# VESC_KS75600_main_power.net
KiCad netlist of a schematic drawn in Altium Designer
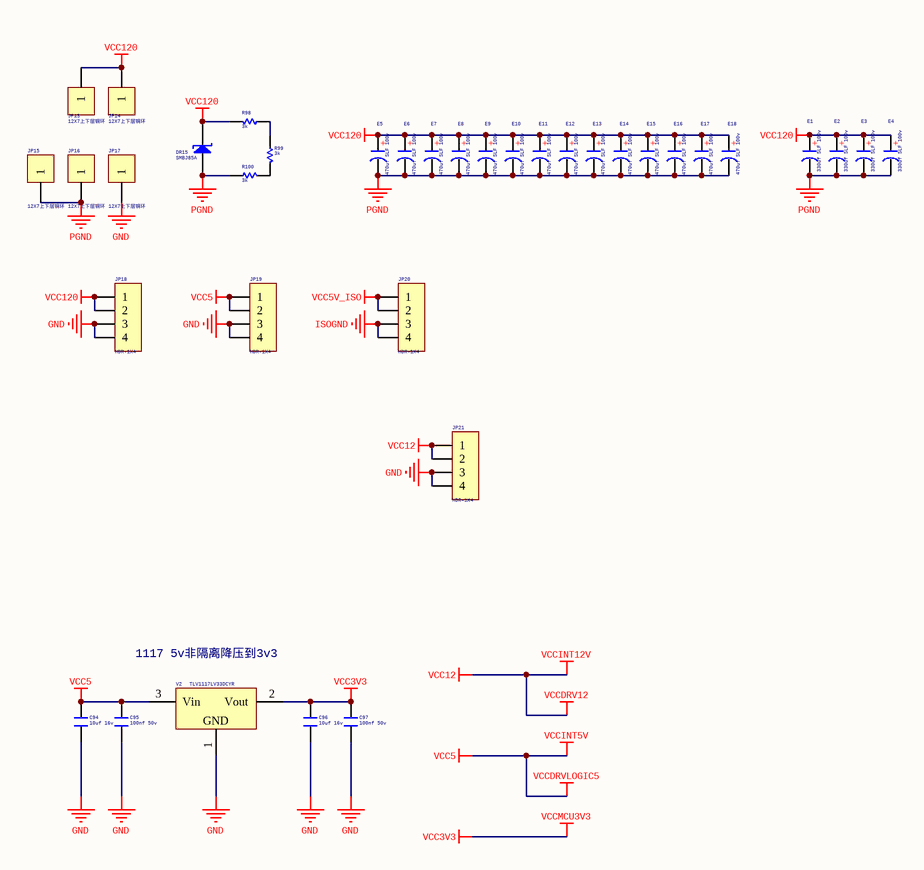
[diagram p0: VESC_KS75600_main_power.SchDoc]

(export (version "E")
  (design (tool "Eeschema 10.0.6"))
  (components
    (comp (ref "C94")
      (value "10uf 16v")
      (footprint "C 0805")
      (description "无极性贴片电容")
      (fields (field (name "VOLTAGE") "16v"))
      (libsource (lib "电阻-电容-电感") (part "C"))
    )
    (comp (ref "C95")
      (value "100nf 50v")
      (footprint "C 0603")
      (description "无极性贴片电容")
      (fields (field (name "VOLTAGE") "50v"))
      (libsource (lib "电阻-电容-电感") (part "C"))
    )
    (comp (ref "C96")
      (value "10uf 16v")
      (footprint "C 0805")
      (description "无极性贴片电容")
      (fields (field (name "VOLTAGE") "16v"))
      (libsource (lib "电阻-电容-电感") (part "C"))
    )
    (comp (ref "C97")
      (value "100nf 50v")
      (footprint "C 0603")
      (description "无极性贴片电容")
      (fields (field (name "VOLTAGE") "50v"))
      (libsource (lib "电阻-电容-电感") (part "C"))
    )
    (comp (ref "DR15")
      (value "SMBJ85A")
      (footprint "SMB")
      (description "瞬态电压抑制二极管(单向)")
      (libsource (lib "二极管-整流桥") (part "DR_S"))
    )
    (comp (ref "E1")
      (value "330uf SLF 100v")
      (footprint "CAP 5.0*13.5*26")
      (description "直插电解电容")
      (fields (field (name "VOLTAGE") "100v"))
      (libsource (lib "电阻-电容-电感") (part "C-CAP"))
    )
    (comp (ref "E2")
      (value "330uf SLF 100v")
      (footprint "CAP 5.0*13.5*26")
      (description "直插电解电容")
      (fields (field (name "VOLTAGE") "100v"))
      (libsource (lib "电阻-电容-电感") (part "C-CAP"))
    )
    (comp (ref "E3")
      (value "330uf SLF 100v")
      (footprint "CAP 5.0*13.5*26")
      (description "直插电解电容")
      (fields (field (name "VOLTAGE") "100v"))
      (libsource (lib "电阻-电容-电感") (part "C-CAP"))
    )
    (comp (ref "E4")
      (value "330uf SLF 100v")
      (footprint "CAP 5.0*13.5*26")
      (description "直插电解电容")
      (fields (field (name "VOLTAGE") "100v"))
      (libsource (lib "电阻-电容-电感") (part "C-CAP"))
    )
    (comp (ref "E5")
      (value "470uf SLF 100v")
      (footprint "CAP 7.5*16.5*27")
      (description "直插电解电容")
      (fields (field (name "VOLTAGE") "100v"))
      (libsource (lib "电阻-电容-电感") (part "C-CAP"))
    )
    (comp (ref "E6")
      (value "470uf SLF 100v")
      (footprint "CAP 7.5*16.5*27")
      (description "直插电解电容")
      (fields (field (name "VOLTAGE") "100v"))
      (libsource (lib "电阻-电容-电感") (part "C-CAP"))
    )
    (comp (ref "E7")
      (value "470uf SLF 100v")
      (footprint "CAP 7.5*16.5*27")
      (description "直插电解电容")
      (fields (field (name "VOLTAGE") "100v"))
      (libsource (lib "电阻-电容-电感") (part "C-CAP"))
    )
    (comp (ref "E8")
      (value "470uf SLF 100v")
      (footprint "CAP 7.5*16.5*27")
      (description "直插电解电容")
      (fields (field (name "VOLTAGE") "100v"))
      (libsource (lib "电阻-电容-电感") (part "C-CAP"))
    )
    (comp (ref "E9")
      (value "470uf SLF 100v")
      (footprint "CAP 7.5*16.5*27")
      (description "直插电解电容")
      (fields (field (name "VOLTAGE") "100v"))
      (libsource (lib "电阻-电容-电感") (part "C-CAP"))
    )
    (comp (ref "E10")
      (value "470uf SLF 100v")
      (footprint "CAP 7.5*16.5*27")
      (description "直插电解电容")
      (fields (field (name "VOLTAGE") "100v"))
      (libsource (lib "电阻-电容-电感") (part "C-CAP"))
    )
    (comp (ref "E11")
      (value "470uf SLF 100v")
      (footprint "CAP 7.5*16.5*27")
      (description "直插电解电容")
      (fields (field (name "VOLTAGE") "100v"))
      (libsource (lib "电阻-电容-电感") (part "C-CAP"))
    )
    (comp (ref "E12")
      (value "470uf SLF 100v")
      (footprint "CAP 7.5*16.5*27")
      (description "直插电解电容")
      (fields (field (name "VOLTAGE") "100v"))
      (libsource (lib "电阻-电容-电感") (part "C-CAP"))
    )
    (comp (ref "E13")
      (value "470uf SLF 100v")
      (footprint "CAP 7.5*16.5*27")
      (description "直插电解电容")
      (fields (field (name "VOLTAGE") "100v"))
      (libsource (lib "电阻-电容-电感") (part "C-CAP"))
    )
    (comp (ref "E14")
      (value "470uf SLF 100v")
      (footprint "CAP 7.5*16.5*27")
      (description "直插电解电容")
      (fields (field (name "VOLTAGE") "100v"))
      (libsource (lib "电阻-电容-电感") (part "C-CAP"))
    )
    (comp (ref "E15")
      (value "470uf SLF 100v")
      (footprint "CAP 7.5*16.5*27")
      (description "直插电解电容")
      (fields (field (name "VOLTAGE") "100v"))
      (libsource (lib "电阻-电容-电感") (part "C-CAP"))
    )
    (comp (ref "E16")
      (value "470uf SLF 100v")
      (footprint "CAP 7.5*16.5*27")
      (description "直插电解电容")
      (fields (field (name "VOLTAGE") "100v"))
      (libsource (lib "电阻-电容-电感") (part "C-CAP"))
    )
    (comp (ref "E17")
      (value "470uf SLF 100v")
      (footprint "CAP 7.5*16.5*27")
      (description "直插电解电容")
      (fields (field (name "VOLTAGE") "100v"))
      (libsource (lib "电阻-电容-电感") (part "C-CAP"))
    )
    (comp (ref "E18")
      (value "470uf SLF 100v")
      (footprint "CAP 7.5*16.5*27")
      (description "直插电解电容")
      (fields (field (name "VOLTAGE") "100v"))
      (libsource (lib "电阻-电容-电感") (part "C-CAP"))
    )
    (comp (ref "JP13")
      (value "12X7上下层铜环")
      (footprint "12x7上下层铜环")
      (description "1P接插件")
      (libsource (lib "") (part "Header 1_1"))
    )
    (comp (ref "JP14")
      (value "12X7上下层铜环")
      (footprint "12x7上下层铜环")
      (description "1P接插件")
      (libsource (lib "") (part "Header 1_1"))
    )
    (comp (ref "JP15")
      (value "12X7上下层铜环")
      (footprint "12x7上下层铜环")
      (description "1P接插件")
      (libsource (lib "接插件") (part "Header 1"))
    )
    (comp (ref "JP16")
      (value "12X7上下层铜环")
      (footprint "12x7上下层铜环")
      (description "1P接插件")
      (libsource (lib "接插件") (part "Header 1"))
    )
    (comp (ref "JP17")
      (value "12X7上下层铜环")
      (footprint "12x7上下层铜环")
      (description "1P接插件")
      (libsource (lib "接插件") (part "Header 1"))
    )
    (comp (ref "JP18")
      (value "HDR-1X4")
      (footprint "HDR-1X4")
      (description "4P接插件")
      (libsource (lib "接插件") (part "Header 4"))
    )
    (comp (ref "JP19")
      (value "HDR-1X4")
      (footprint "HDR-1X4")
      (description "4P接插件")
      (libsource (lib "接插件") (part "Header 4"))
    )
    (comp (ref "JP20")
      (value "HDR-1X4")
      (footprint "HDR-1X4")
      (description "4P接插件")
      (libsource (lib "接插件") (part "Header 4"))
    )
    (comp (ref "JP21")
      (value "HDR-1X4")
      (footprint "HDR-1X4")
      (description "4P接插件")
      (libsource (lib "接插件") (part "Header 4"))
    )
    (comp (ref "R98")
      (value "3k")
      (footprint "R 2512")
      (description "贴片电阻")
      (libsource (lib "电阻-电容-电感") (part "R"))
    )
    (comp (ref "R99")
      (value "3k")
      (footprint "R 2512")
      (description "贴片电阻")
      (libsource (lib "电阻-电容-电感") (part "R"))
    )
    (comp (ref "R100")
      (value "3k")
      (footprint "R 2512")
      (description "贴片电阻")
      (libsource (lib "电阻-电容-电感") (part "R"))
    )
    (comp (ref "V2")
      (value "TLV1117LV33DCYR")
      (footprint "SOT223_L")
      (description "三端稳压芯片")
      (libsource (lib "IC芯片") (part "AMS1117"))
    )
  )
  (nets
    (net (code "1") (name "GND") (class "Default")
      (node (ref "C94") (pin "2") (pinfunction "2_2") (pintype "passive"))
      (node (ref "C95") (pin "2") (pinfunction "2_2") (pintype "passive"))
      (node (ref "C96") (pin "2") (pinfunction "2_2") (pintype "passive"))
      (node (ref "C97") (pin "2") (pinfunction "2_2") (pintype "passive"))
      (node (ref "JP17") (pin "1") (pinfunction "1_1") (pintype "passive"))
      (node (ref "JP18") (pin "3") (pinfunction "3_3") (pintype "passive"))
      (node (ref "JP18") (pin "4") (pinfunction "4_4") (pintype "passive"))
      (node (ref "JP19") (pin "3") (pinfunction "3_3") (pintype "passive"))
      (node (ref "JP19") (pin "4") (pinfunction "4_4") (pintype "passive"))
      (node (ref "JP21") (pin "3") (pinfunction "3_3") (pintype "passive"))
      (node (ref "JP21") (pin "4") (pinfunction "4_4") (pintype "passive"))
      (node (ref "V2") (pin "1") (pinfunction "GND_1") (pintype "passive"))
    )
    (net (code "2") (name "ISOGND") (class "Default")
      (node (ref "JP20") (pin "3") (pinfunction "3_3") (pintype "passive"))
      (node (ref "JP20") (pin "4") (pinfunction "4_4") (pintype "passive"))
    )
    (net (code "3") (name "Net-(R98-Pad1)") (class "Default")
      (node (ref "R98") (pin "1") (pinfunction "1_1") (pintype "passive"))
      (node (ref "R99") (pin "1") (pinfunction "1_1") (pintype "passive"))
    )
    (net (code "4") (name "Net-(R100-Pad2)") (class "Default")
      (node (ref "R100") (pin "2") (pinfunction "2_2") (pintype "passive"))
      (node (ref "R99") (pin "2") (pinfunction "2_2") (pintype "passive"))
    )
    (net (code "5") (name "PGND") (class "Default")
      (node (ref "DR15") (pin "1") (pinfunction "A_1") (pintype "passive"))
      (node (ref "E1") (pin "2") (pinfunction "2_2") (pintype "passive"))
      (node (ref "E10") (pin "2") (pinfunction "2_2") (pintype "passive"))
      (node (ref "E11") (pin "2") (pinfunction "2_2") (pintype "passive"))
      (node (ref "E12") (pin "2") (pinfunction "2_2") (pintype "passive"))
      (node (ref "E13") (pin "2") (pinfunction "2_2") (pintype "passive"))
      (node (ref "E14") (pin "2") (pinfunction "2_2") (pintype "passive"))
      (node (ref "E15") (pin "2") (pinfunction "2_2") (pintype "passive"))
      (node (ref "E16") (pin "2") (pinfunction "2_2") (pintype "passive"))
      (node (ref "E17") (pin "2") (pinfunction "2_2") (pintype "passive"))
      (node (ref "E18") (pin "2") (pinfunction "2_2") (pintype "passive"))
      (node (ref "E2") (pin "2") (pinfunction "2_2") (pintype "passive"))
      (node (ref "E3") (pin "2") (pinfunction "2_2") (pintype "passive"))
      (node (ref "E4") (pin "2") (pinfunction "2_2") (pintype "passive"))
      (node (ref "E5") (pin "2") (pinfunction "2_2") (pintype "passive"))
      (node (ref "E6") (pin "2") (pinfunction "2_2") (pintype "passive"))
      (node (ref "E7") (pin "2") (pinfunction "2_2") (pintype "passive"))
      (node (ref "E8") (pin "2") (pinfunction "2_2") (pintype "passive"))
      (node (ref "E9") (pin "2") (pinfunction "2_2") (pintype "passive"))
      (node (ref "JP15") (pin "1") (pinfunction "1_1") (pintype "passive"))
      (node (ref "JP16") (pin "1") (pinfunction "1_1") (pintype "passive"))
      (node (ref "R100") (pin "1") (pinfunction "1_1") (pintype "passive"))
    )
    (net (code "6") (name "VCC3V3") (class "Default")
      (node (ref "C96") (pin "1") (pinfunction "1_1") (pintype "passive"))
      (node (ref "C97") (pin "1") (pinfunction "1_1") (pintype "passive"))
      (node (ref "V2") (pin "2") (pinfunction "Vout_2") (pintype "passive"))
    )
    (net (code "7") (name "VCC5") (class "Default")
      (node (ref "C94") (pin "1") (pinfunction "1_1") (pintype "passive"))
      (node (ref "C95") (pin "1") (pinfunction "1_1") (pintype "passive"))
      (node (ref "JP19") (pin "1") (pinfunction "1_1") (pintype "passive"))
      (node (ref "JP19") (pin "2") (pinfunction "2_2") (pintype "passive"))
      (node (ref "V2") (pin "3") (pinfunction "Vin_3") (pintype "passive"))
    )
    (net (code "8") (name "VCC5V_ISO") (class "Default")
      (node (ref "JP20") (pin "1") (pinfunction "1_1") (pintype "passive"))
      (node (ref "JP20") (pin "2") (pinfunction "2_2") (pintype "passive"))
    )
    (net (code "9") (name "VCC12") (class "Default")
      (node (ref "JP21") (pin "1") (pinfunction "1_1") (pintype "passive"))
      (node (ref "JP21") (pin "2") (pinfunction "2_2") (pintype "passive"))
    )
    (net (code "10") (name "VCC120") (class "Default")
      (node (ref "DR15") (pin "2") (pinfunction "K_2") (pintype "passive"))
      (node (ref "E1") (pin "1") (pinfunction "1_1") (pintype "passive"))
      (node (ref "E10") (pin "1") (pinfunction "1_1") (pintype "passive"))
      (node (ref "E11") (pin "1") (pinfunction "1_1") (pintype "passive"))
      (node (ref "E12") (pin "1") (pinfunction "1_1") (pintype "passive"))
      (node (ref "E13") (pin "1") (pinfunction "1_1") (pintype "passive"))
      (node (ref "E14") (pin "1") (pinfunction "1_1") (pintype "passive"))
      (node (ref "E15") (pin "1") (pinfunction "1_1") (pintype "passive"))
      (node (ref "E16") (pin "1") (pinfunction "1_1") (pintype "passive"))
      (node (ref "E17") (pin "1") (pinfunction "1_1") (pintype "passive"))
      (node (ref "E18") (pin "1") (pinfunction "1_1") (pintype "passive"))
      (node (ref "E2") (pin "1") (pinfunction "1_1") (pintype "passive"))
      (node (ref "E3") (pin "1") (pinfunction "1_1") (pintype "passive"))
      (node (ref "E4") (pin "1") (pinfunction "1_1") (pintype "passive"))
      (node (ref "E5") (pin "1") (pinfunction "1_1") (pintype "passive"))
      (node (ref "E6") (pin "1") (pinfunction "1_1") (pintype "passive"))
      (node (ref "E7") (pin "1") (pinfunction "1_1") (pintype "passive"))
      (node (ref "E8") (pin "1") (pinfunction "1_1") (pintype "passive"))
      (node (ref "E9") (pin "1") (pinfunction "1_1") (pintype "passive"))
      (node (ref "JP13") (pin "1") (pinfunction "1_1") (pintype "passive"))
      (node (ref "JP14") (pin "1") (pinfunction "1_1") (pintype "passive"))
      (node (ref "JP18") (pin "1") (pinfunction "1_1") (pintype "passive"))
      (node (ref "JP18") (pin "2") (pinfunction "2_2") (pintype "passive"))
      (node (ref "R98") (pin "2") (pinfunction "2_2") (pintype "passive"))
    )
  )
)
